# Neo7m_eval_board.net
KiCad netlist of a schematic drawn in EAGLE
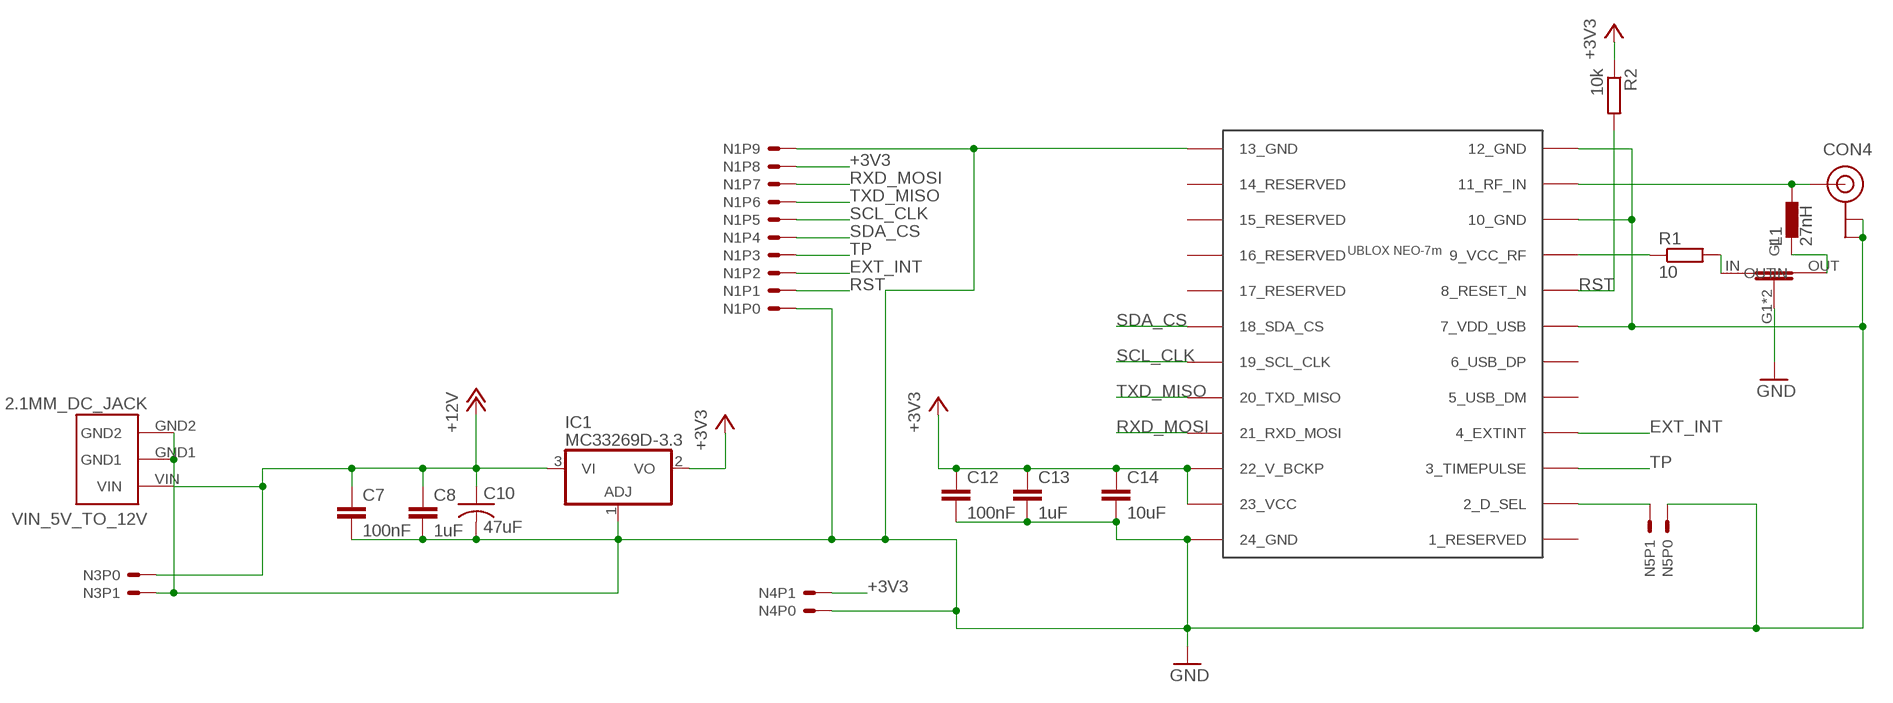
[diagram p0: schematic, sheet 1]

(export (version "E")
  (design (tool "Eeschema 10.0.6"))
  (components
    (comp (ref "C7")
      (value "100nF")
      (footprint "eagle-import:C1206")
      (libsource (lib "eagle-import") (part "C-EUC1206"))
    )
    (comp (ref "C8")
      (value "1uF")
      (footprint "eagle-import:C1206")
      (libsource (lib "eagle-import") (part "C-EUC1206"))
    )
    (comp (ref "C10")
      (value "47uF")
      (footprint "eagle-import:47UF_AL_SMD")
      (libsource (lib "eagle-import") (part "47UF_AL_SMD"))
    )
    (comp (ref "C12")
      (value "100nF")
      (footprint "eagle-import:C1206")
      (libsource (lib "eagle-import") (part "C-EUC1206"))
    )
    (comp (ref "C13")
      (value "1uF")
      (footprint "eagle-import:C1206")
      (libsource (lib "eagle-import") (part "C-EUC1206"))
    )
    (comp (ref "C14")
      (value "10uF")
      (footprint "eagle-import:C1206")
      (libsource (lib "eagle-import") (part "C-EUC1206"))
    )
    (comp (ref "CON4")
      (value "U.FL")
      (footprint "eagle-import:U.FL")
      (libsource (lib "eagle-import") (part "U.FL"))
    )
    (comp (ref "IC1")
      (value "MC33269D-3.3")
      (footprint "eagle-import:DPACK")
      (libsource (lib "eagle-import") (part "MC33269?D-3.3"))
    )
    (comp (ref "L1")
      (value "27nH")
      (footprint "eagle-import:0402")
      (libsource (lib "eagle-import") (part "BLM15HB221SN1"))
    )
    (comp (ref "N1")
      (value "10PINHEADER")
      (footprint "eagle-import:10PINHEADER")
      (libsource (lib "eagle-import") (part "10PINHEADER"))
    )
    (comp (ref "N3")
      (value "2PINHEADER")
      (footprint "eagle-import:2PINHEADER")
      (libsource (lib "eagle-import") (part "2PINHEADER"))
    )
    (comp (ref "N4")
      (value "2PINHEADER")
      (footprint "eagle-import:2PINHEADER")
      (libsource (lib "eagle-import") (part "2PINHEADER"))
    )
    (comp (ref "N5")
      (value "2PINHEADER")
      (footprint "eagle-import:2PINHEADER")
      (libsource (lib "eagle-import") (part "2PINHEADER"))
    )
    (comp (ref "R1")
      (value "10")
      (footprint "eagle-import:R1206")
      (libsource (lib "eagle-import") (part "R-EU_R1206"))
    )
    (comp (ref "R2")
      (value "10k")
      (footprint "eagle-import:R1206")
      (libsource (lib "eagle-import") (part "R-EU_R1206"))
    )
    (comp (ref "U$1")
      (value "FEEDTHRU_CAP_1206")
      (footprint "eagle-import:FEEDTHRU_CAP_1206")
      (libsource (lib "eagle-import") (part "FEEDTHRU_CAP_1206"))
    )
    (comp (ref "U$4")
      (value "UBLOX_NEO7M")
      (footprint "eagle-import:UBLOX_NEO7M")
      (libsource (lib "eagle-import") (part "UBLOX_NEO7M"))
    )
    (comp (ref "VIN_5V_TO_12V")
      (value "2.1MM_DC_JACK")
      (footprint "eagle-import:2.1MM_DC_JACK")
      (libsource (lib "eagle-import") (part "2.1MM_DC_JACK"))
    )
  )
  (nets
    (net (code "1") (name "+3V3") (class "Default")
      (node (ref "C12") (pin "1") (pinfunction "1_1") (pintype "passive"))
      (node (ref "C13") (pin "1") (pinfunction "1_1") (pintype "passive"))
      (node (ref "C14") (pin "1") (pinfunction "1_1") (pintype "passive"))
      (node (ref "IC1") (pin "2") (pinfunction "VO_2") (pintype "passive"))
      (node (ref "N1") (pin "P8") (pinfunction "S_P8") (pintype "passive"))
      (node (ref "N4") (pin "P1") (pinfunction "S_P1") (pintype "passive"))
      (node (ref "R2") (pin "1") (pinfunction "1_1") (pintype "passive"))
      (node (ref "U$4") (pin "22_V_BCKP") (pinfunction "22_V_BCKP_22_V_BCKP") (pintype "bidirectional"))
      (node (ref "U$4") (pin "23_VCC") (pinfunction "23_VCC_23_VCC") (pintype "bidirectional"))
    )
    (net (code "2") (name "+12V") (class "Default")
      (node (ref "C10") (pin "P$1") (pinfunction "1_P$1") (pintype "passive"))
      (node (ref "C7") (pin "1") (pinfunction "1_1") (pintype "passive"))
      (node (ref "C8") (pin "1") (pinfunction "1_1") (pintype "passive"))
      (node (ref "IC1") (pin "3") (pinfunction "VI_3") (pintype "input"))
      (node (ref "N3") (pin "P0") (pinfunction "S_P0") (pintype "passive"))
      (node (ref "VIN_5V_TO_12V") (pin "VIN") (pinfunction "VIN_VIN") (pintype "power_in"))
    )
    (net (code "3") (name "/EXT_INT") (class "Default")
      (node (ref "N1") (pin "P2") (pinfunction "S_P2") (pintype "passive"))
      (node (ref "U$4") (pin "4_EXTINT") (pinfunction "4_EXTINT_4_EXTINT") (pintype "bidirectional"))
    )
    (net (code "4") (name "/RST") (class "Default")
      (node (ref "N1") (pin "P1") (pinfunction "S_P1") (pintype "passive"))
      (node (ref "R2") (pin "2") (pinfunction "2_2") (pintype "passive"))
      (node (ref "U$4") (pin "8_RESET_N") (pinfunction "8_RESET_N_8_RESET_N") (pintype "bidirectional"))
    )
    (net (code "5") (name "/RXD_MOSI") (class "Default")
      (node (ref "N1") (pin "P7") (pinfunction "S_P7") (pintype "passive"))
      (node (ref "U$4") (pin "21_RXD_MOSI") (pinfunction "21_RXD_MOSI_21_RXD_MOSI") (pintype "bidirectional"))
    )
    (net (code "6") (name "/SCL_CLK") (class "Default")
      (node (ref "N1") (pin "P5") (pinfunction "S_P5") (pintype "passive"))
      (node (ref "U$4") (pin "19_SCL_CLK") (pinfunction "19_SCL_CLK_19_SCL_CLK") (pintype "bidirectional"))
    )
    (net (code "7") (name "/SDA_CS") (class "Default")
      (node (ref "N1") (pin "P4") (pinfunction "S_P4") (pintype "passive"))
      (node (ref "U$4") (pin "18_SDA_CS") (pinfunction "18_SDA_CS_18_SDA_CS") (pintype "bidirectional"))
    )
    (net (code "8") (name "/TP") (class "Default")
      (node (ref "N1") (pin "P3") (pinfunction "S_P3") (pintype "passive"))
      (node (ref "U$4") (pin "3_TIMEPULSE") (pinfunction "3_TIMEPULSE_3_TIMEPULSE") (pintype "bidirectional"))
    )
    (net (code "9") (name "/TXD_MISO") (class "Default")
      (node (ref "N1") (pin "P6") (pinfunction "S_P6") (pintype "passive"))
      (node (ref "U$4") (pin "20_TXD_MISO") (pinfunction "20_TXD_MISO_20_TXD_MISO") (pintype "bidirectional"))
    )
    (net (code "10") (name "GND") (class "Default")
      (node (ref "C10") (pin "P$2") (pinfunction "2_P$2") (pintype "passive"))
      (node (ref "C12") (pin "2") (pinfunction "2_2") (pintype "passive"))
      (node (ref "C13") (pin "2") (pinfunction "2_2") (pintype "passive"))
      (node (ref "C14") (pin "2") (pinfunction "2_2") (pintype "passive"))
      (node (ref "C7") (pin "2") (pinfunction "2_2") (pintype "passive"))
      (node (ref "C8") (pin "2") (pinfunction "2_2") (pintype "passive"))
      (node (ref "CON4") (pin "P$1") (pinfunction "GND_P$1") (pintype "bidirectional"))
      (node (ref "CON4") (pin "P$2") (pinfunction "GND_P$2") (pintype "bidirectional"))
      (node (ref "IC1") (pin "1") (pinfunction "ADJ_1") (pintype "input"))
      (node (ref "N1") (pin "P0") (pinfunction "S_P0") (pintype "passive"))
      (node (ref "N1") (pin "P9") (pinfunction "S_P9") (pintype "passive"))
      (node (ref "N3") (pin "P1") (pinfunction "S_P1") (pintype "passive"))
      (node (ref "N4") (pin "P0") (pinfunction "S_P0") (pintype "passive"))
      (node (ref "N5") (pin "P0") (pinfunction "S_P0") (pintype "passive"))
      (node (ref "U$1") (pin "G1") (pinfunction "G1_G1") (pintype "output"))
      (node (ref "U$1") (pin "G2") (pinfunction "G1_G2") (pintype "output"))
      (node (ref "U$4") (pin "10_GND") (pinfunction "10_GND_10_GND") (pintype "bidirectional"))
      (node (ref "U$4") (pin "12_GND") (pinfunction "12_GND_12_GND") (pintype "bidirectional"))
      (node (ref "U$4") (pin "13_GND") (pinfunction "13_GND_13_GND") (pintype "bidirectional"))
      (node (ref "U$4") (pin "24_GND") (pinfunction "24_GND_24_GND") (pintype "bidirectional"))
      (node (ref "U$4") (pin "7_VDD_USB") (pinfunction "7_VDD_USB_7_VDD_USB") (pintype "bidirectional"))
      (node (ref "VIN_5V_TO_12V") (pin "GND1") (pinfunction "GND1_GND1") (pintype "bidirectional"))
      (node (ref "VIN_5V_TO_12V") (pin "GND2") (pinfunction "GND2_GND2") (pintype "bidirectional"))
    )
    (net (code "11") (name "Net-(CON4-SIGNAL)") (class "Default")
      (node (ref "CON4") (pin "P$3") (pinfunction "SIGNAL_P$3") (pintype "bidirectional"))
      (node (ref "L1") (pin "2") (pinfunction "2_2") (pintype "passive"))
      (node (ref "U$4") (pin "11_RF_IN") (pinfunction "11_RF_IN_11_RF_IN") (pintype "bidirectional"))
    )
    (net (code "12") (name "Net-(L1-Pad1)") (class "Default")
      (node (ref "L1") (pin "1") (pinfunction "1_1") (pintype "passive"))
      (node (ref "U$1") (pin "OUT") (pinfunction "OUT_OUT") (pintype "output"))
    )
    (net (code "13") (name "Net-(N5B-S)") (class "Default")
      (node (ref "N5") (pin "P1") (pinfunction "S_P1") (pintype "passive"))
      (node (ref "U$4") (pin "2_D_SEL") (pinfunction "2_D_SEL_2_D_SEL") (pintype "bidirectional"))
    )
    (net (code "14") (name "Net-(R1-Pad1)") (class "Default")
      (node (ref "R1") (pin "1") (pinfunction "1_1") (pintype "passive"))
      (node (ref "U$4") (pin "9_VCC_RF") (pinfunction "9_VCC_RF_9_VCC_RF") (pintype "bidirectional"))
    )
    (net (code "15") (name "Net-(R1-Pad2)") (class "Default")
      (node (ref "R1") (pin "2") (pinfunction "2_2") (pintype "passive"))
      (node (ref "U$1") (pin "IN") (pinfunction "IN_IN") (pintype "input"))
    )
    (net (code "16") (name "unconnected-(U$4-Pad1_RESERVED)") (class "Default")
      (node (ref "U$4") (pin "1_RESERVED") (pinfunction "1_RESERVED_1_RESERVED") (pintype "bidirectional"))
    )
    (net (code "17") (name "unconnected-(U$4-Pad5_USB_DM)") (class "Default")
      (node (ref "U$4") (pin "5_USB_DM") (pinfunction "5_USB_DM_5_USB_DM") (pintype "bidirectional"))
    )
    (net (code "18") (name "unconnected-(U$4-Pad6_USB_DP)") (class "Default")
      (node (ref "U$4") (pin "6_USB_DP") (pinfunction "6_USB_DP_6_USB_DP") (pintype "bidirectional"))
    )
    (net (code "19") (name "unconnected-(U$4-Pad14_RESERVED)") (class "Default")
      (node (ref "U$4") (pin "14_RESERVED") (pinfunction "14_RESERVED_14_RESERVED") (pintype "bidirectional"))
    )
    (net (code "20") (name "unconnected-(U$4-Pad15_RESERVED)") (class "Default")
      (node (ref "U$4") (pin "15_RESERVED") (pinfunction "15_RESERVED_15_RESERVED") (pintype "bidirectional"))
    )
    (net (code "21") (name "unconnected-(U$4-Pad16_RESERVED)") (class "Default")
      (node (ref "U$4") (pin "16_RESERVED") (pinfunction "16_RESERVED_16_RESERVED") (pintype "bidirectional"))
    )
    (net (code "22") (name "unconnected-(U$4-Pad17_RESERVED)") (class "Default")
      (node (ref "U$4") (pin "17_RESERVED") (pinfunction "17_RESERVED_17_RESERVED") (pintype "bidirectional"))
    )
  )
)
